# mde_v1.net
KiCad netlist of a schematic drawn in EAGLE
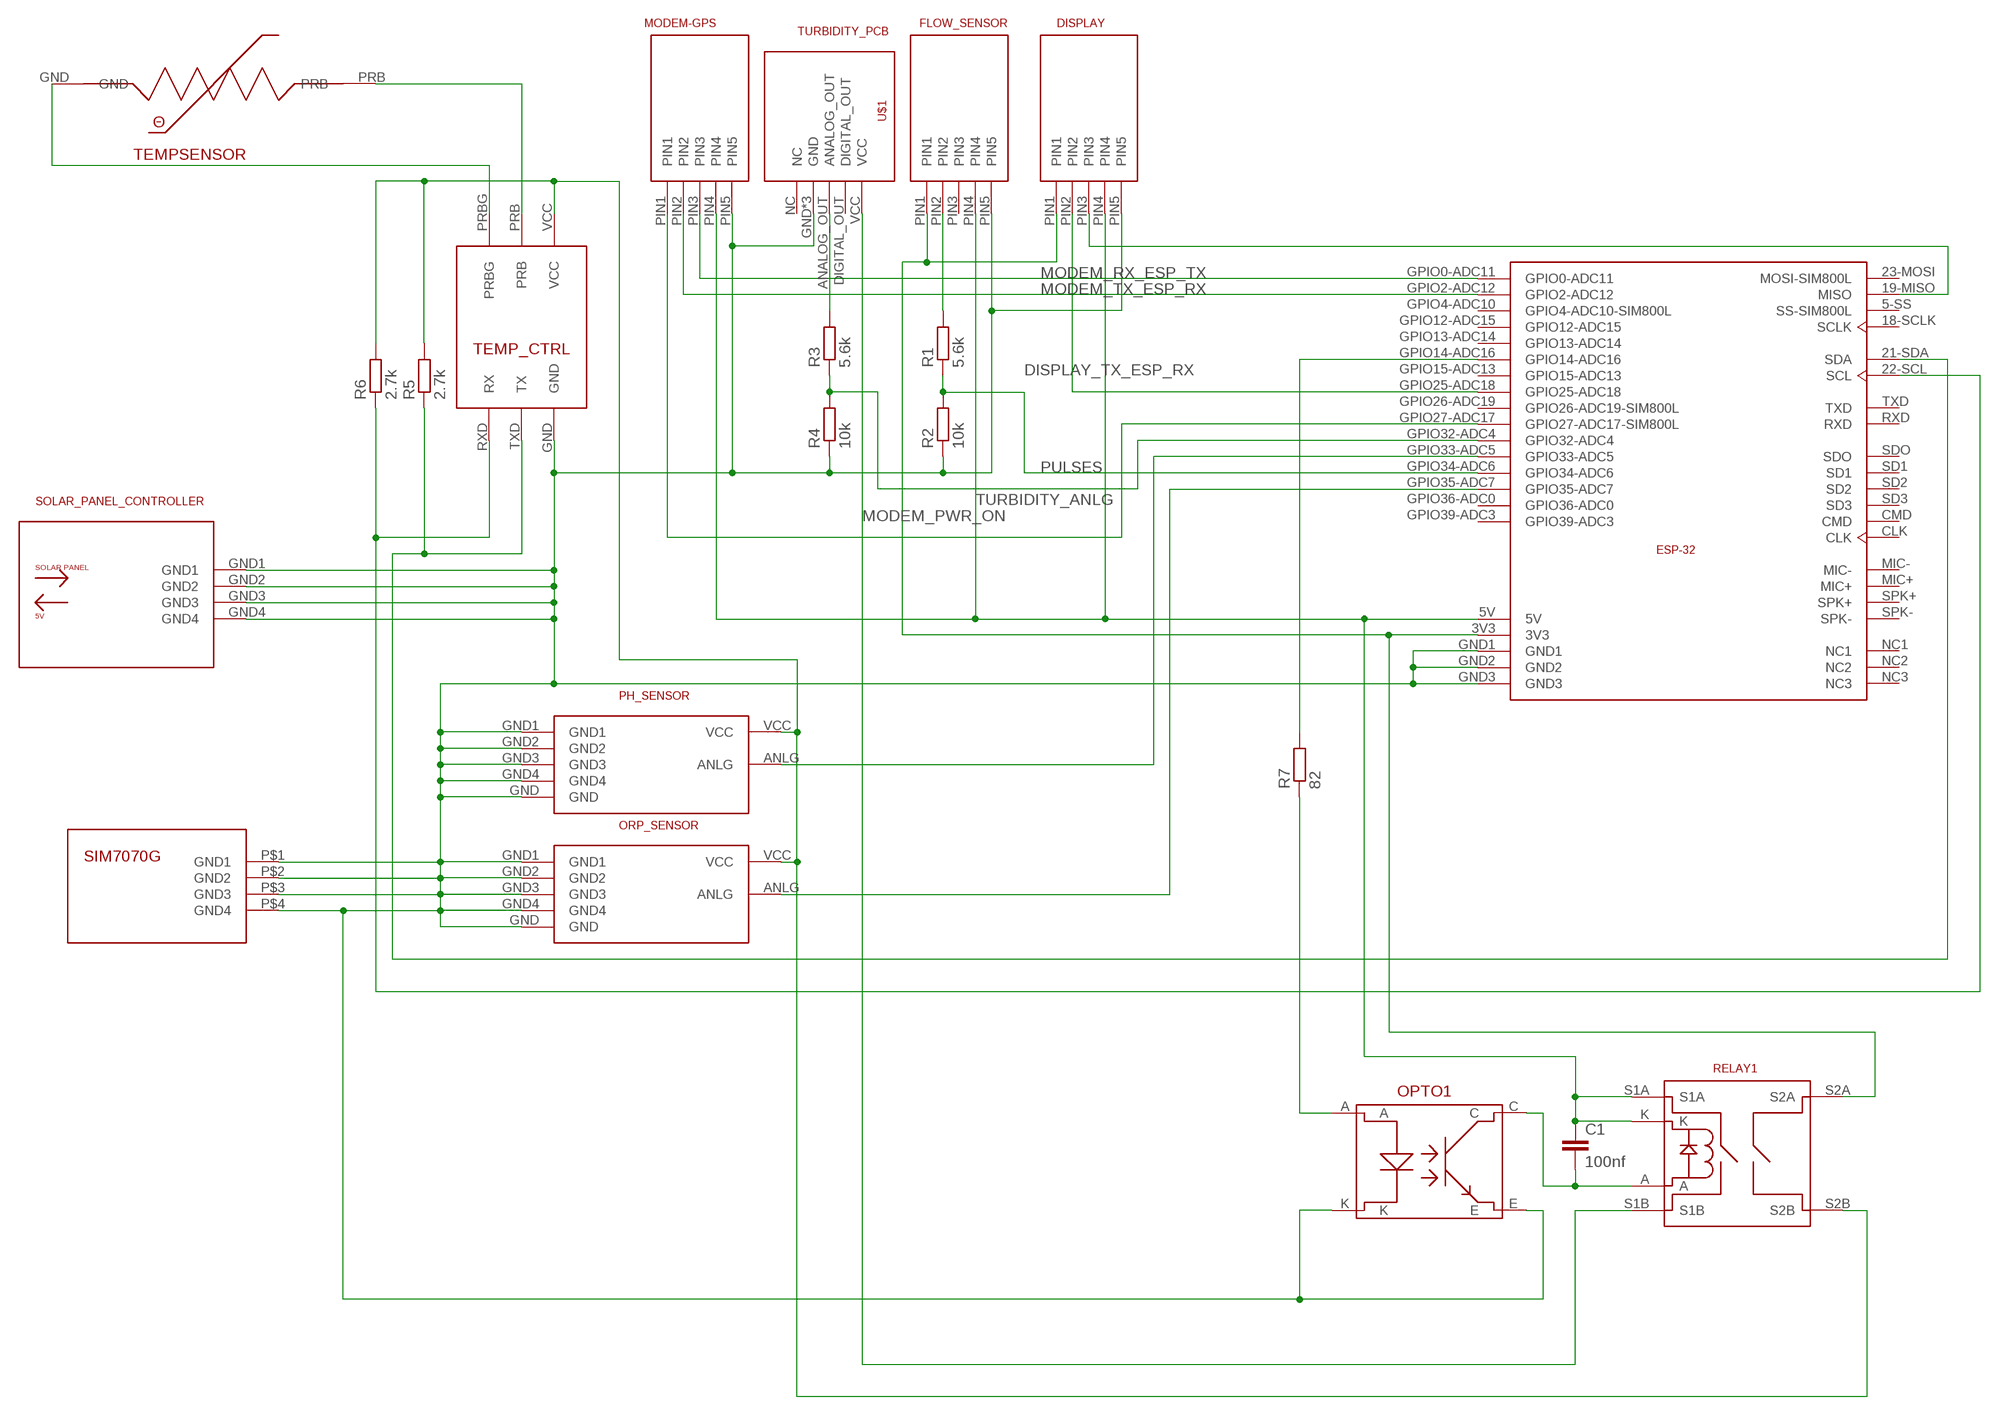
[diagram p0: schematic, sheet 1]

(export (version "E")
  (design (tool "Eeschema 10.0.6"))
  (components
    (comp (ref "C1")
      (value "100nf")
      (footprint "eagle-import:C2.5-3")
      (libsource (lib "eagle-import") (part "C2,5-3"))
    )
    (comp (ref "DISPLAY")
      (value "CONNECTOR-JSTXH-5")
      (footprint "eagle-import:CONNECTOR-JSTXH-5")
      (libsource (lib "eagle-import") (part "CONNECTOR-JSTXH-5"))
    )
    (comp (ref "ESP-32")
      (value "ESP32-TTGO-SIM800L")
      (footprint "eagle-import:ESP32-TTGO-SIM800L")
      (libsource (lib "eagle-import") (part "ESP32-TTGO-SIM800L"))
    )
    (comp (ref "FLOW_SENSOR")
      (value "CONNECTOR-JSTXH-5")
      (footprint "eagle-import:CONNECTOR-JSTXH-5")
      (libsource (lib "eagle-import") (part "CONNECTOR-JSTXH-5"))
    )
    (comp (ref "MODEM-GPS")
      (value "CONNECTOR-JSTXH-5")
      (footprint "eagle-import:CONNECTOR-JSTXH-5")
      (libsource (lib "eagle-import") (part "CONNECTOR-JSTXH-5"))
    )
    (comp (ref "OPTO1")
      (value "K817P")
      (footprint "eagle-import:K817P")
      (libsource (lib "eagle-import") (part "K817P"))
    )
    (comp (ref "ORP_SENSOR")
      (value "GRAVITY-PCB")
      (footprint "eagle-import:GRAVITY-PCB")
      (libsource (lib "eagle-import") (part "GRAVITY-PCB"))
    )
    (comp (ref "PH_SENSOR")
      (value "GRAVITY-PCB")
      (footprint "eagle-import:GRAVITY-PCB")
      (libsource (lib "eagle-import") (part "GRAVITY-PCB"))
    )
    (comp (ref "R1")
      (value "5.6k")
      (footprint "eagle-import:0207_10")
      (libsource (lib "eagle-import") (part "R-EU_0207/10"))
    )
    (comp (ref "R2")
      (value "10k")
      (footprint "eagle-import:0207_10")
      (libsource (lib "eagle-import") (part "R-EU_0207/10"))
    )
    (comp (ref "R3")
      (value "5.6k")
      (footprint "eagle-import:0207_10")
      (libsource (lib "eagle-import") (part "R-EU_0207/10"))
    )
    (comp (ref "R4")
      (value "10k")
      (footprint "eagle-import:0207_10")
      (libsource (lib "eagle-import") (part "R-EU_0207/10"))
    )
    (comp (ref "R5")
      (value "2.7k")
      (footprint "eagle-import:0207_10")
      (libsource (lib "eagle-import") (part "R-EU_0207/10"))
    )
    (comp (ref "R6")
      (value "2.7k")
      (footprint "eagle-import:0207_10")
      (libsource (lib "eagle-import") (part "R-EU_0207/10"))
    )
    (comp (ref "R7")
      (value "82")
      (footprint "eagle-import:0207_10")
      (libsource (lib "eagle-import") (part "R-EU_0207/10"))
    )
    (comp (ref "RELAY1")
      (value "DIP05-2A72-21D")
      (footprint "eagle-import:DIP05-2A72-21D")
      (libsource (lib "eagle-import") (part "DIP05-2A72-21D"))
    )
    (comp (ref "SIM7070G")
      (value "SIM7070G")
      (footprint "eagle-import:SIM7070G")
      (libsource (lib "eagle-import") (part "SIM7070G"))
    )
    (comp (ref "SOLAR_PANEL_CONTROLLER")
      (value "DFR0559")
      (footprint "eagle-import:DFR0559")
      (libsource (lib "eagle-import") (part "DFR0559"))
    )
    (comp (ref "TEMPSENSOR")
      (value "TEMP-PROBE")
      (footprint "eagle-import:TEMP-PROBE")
      (libsource (lib "eagle-import") (part "TEMP-PROBE"))
    )
    (comp (ref "TEMP_CTRL")
      (value "EZO-RTD")
      (footprint "eagle-import:EZO-RTD")
      (libsource (lib "eagle-import") (part "EZO-RTD"))
    )
    (comp (ref "U$1")
      (value "TURBIDITY_PCB")
      (footprint "eagle-import:TURBIDITY_PCB")
      (libsource (lib "eagle-import") (part "TURBIDITY_PCB"))
    )
  )
  (nets
    (net (code "1") (name "/DISPLAY_TX_ESP_RX") (class "Default")
      (node (ref "DISPLAY") (pin "PIN2") (pinfunction "PIN2_PIN2") (pintype "bidirectional"))
      (node (ref "ESP-32") (pin "GPIO25-ADC18") (pinfunction "GPIO25-ADC18_GPIO25-ADC18") (pintype "bidirectional"))
    )
    (net (code "2") (name "/MODEM_PWR_ON") (class "Default")
      (node (ref "ESP-32") (pin "GPIO27-ADC17") (pinfunction "GPIO27-ADC17-SIM800L_GPIO27-ADC17") (pintype "bidirectional"))
      (node (ref "MODEM-GPS") (pin "PIN1") (pinfunction "PIN1_PIN1") (pintype "bidirectional"))
    )
    (net (code "3") (name "/MODEM_RX_ESP_TX") (class "Default")
      (node (ref "ESP-32") (pin "GPIO0-ADC11") (pinfunction "GPIO0-ADC11_GPIO0-ADC11") (pintype "bidirectional"))
      (node (ref "MODEM-GPS") (pin "PIN3") (pinfunction "PIN3_PIN3") (pintype "bidirectional"))
    )
    (net (code "4") (name "/MODEM_TX_ESP_RX") (class "Default")
      (node (ref "ESP-32") (pin "GPIO2-ADC12") (pinfunction "GPIO2-ADC12_GPIO2-ADC12") (pintype "bidirectional"))
      (node (ref "MODEM-GPS") (pin "PIN2") (pinfunction "PIN2_PIN2") (pintype "bidirectional"))
    )
    (net (code "5") (name "/PULSES") (class "Default")
      (node (ref "ESP-32") (pin "GPIO34-ADC6") (pinfunction "GPIO34-ADC6_GPIO34-ADC6") (pintype "bidirectional"))
      (node (ref "R1") (pin "1") (pinfunction "1_1") (pintype "passive"))
      (node (ref "R2") (pin "2") (pinfunction "2_2") (pintype "passive"))
    )
    (net (code "6") (name "/TURBIDITY_ANLG") (class "Default")
      (node (ref "ESP-32") (pin "GPIO32-ADC4") (pinfunction "GPIO32-ADC4_GPIO32-ADC4") (pintype "bidirectional"))
      (node (ref "R3") (pin "1") (pinfunction "1_1") (pintype "passive"))
      (node (ref "R4") (pin "2") (pinfunction "2_2") (pintype "passive"))
    )
    (net (code "7") (name "Net-(C1-Pad1)") (class "Default")
      (node (ref "C1") (pin "1") (pinfunction "1_1") (pintype "passive"))
      (node (ref "DISPLAY") (pin "PIN4") (pinfunction "PIN4_PIN4") (pintype "bidirectional"))
      (node (ref "ESP-32") (pin "5V") (pinfunction "5V_5V") (pintype "power_in"))
      (node (ref "FLOW_SENSOR") (pin "PIN4") (pinfunction "PIN4_PIN4") (pintype "bidirectional"))
      (node (ref "MODEM-GPS") (pin "PIN4") (pinfunction "PIN4_PIN4") (pintype "bidirectional"))
      (node (ref "RELAY1") (pin "K") (pinfunction "K_K") (pintype "bidirectional"))
      (node (ref "RELAY1") (pin "S1A") (pinfunction "S1A_S1A") (pintype "bidirectional"))
    )
    (net (code "8") (name "Net-(C1-Pad2)") (class "Default")
      (node (ref "C1") (pin "2") (pinfunction "2_2") (pintype "passive"))
      (node (ref "OPTO1") (pin "C") (pinfunction "C_C") (pintype "bidirectional"))
      (node (ref "RELAY1") (pin "A") (pinfunction "A_A") (pintype "bidirectional"))
    )
    (net (code "9") (name "Net-(DISPLAY-PadPIN1)") (class "Default")
      (node (ref "DISPLAY") (pin "PIN1") (pinfunction "PIN1_PIN1") (pintype "bidirectional"))
      (node (ref "ESP-32") (pin "3V3") (pinfunction "3V3_3V3") (pintype "power_in"))
      (node (ref "FLOW_SENSOR") (pin "PIN1") (pinfunction "PIN1_PIN1") (pintype "bidirectional"))
      (node (ref "RELAY1") (pin "S2A") (pinfunction "S2A_S2A") (pintype "bidirectional"))
    )
    (net (code "10") (name "Net-(ESP-32-MISO)") (class "Default")
      (node (ref "DISPLAY") (pin "PIN3") (pinfunction "PIN3_PIN3") (pintype "bidirectional"))
      (node (ref "ESP-32") (pin "19-MISO") (pinfunction "MISO_19-MISO") (pintype "input"))
    )
    (net (code "11") (name "Net-(ESP-32-PadGPIO14-ADC16)") (class "Default")
      (node (ref "ESP-32") (pin "GPIO14-ADC16") (pinfunction "GPIO14-ADC16_GPIO14-ADC16") (pintype "bidirectional"))
      (node (ref "R7") (pin "2") (pinfunction "2_2") (pintype "passive"))
    )
    (net (code "12") (name "Net-(ESP-32-PadGPIO33-ADC5)") (class "Default")
      (node (ref "ESP-32") (pin "GPIO33-ADC5") (pinfunction "GPIO33-ADC5_GPIO33-ADC5") (pintype "bidirectional"))
      (node (ref "PH_SENSOR") (pin "ANLG") (pinfunction "ANLG_ANLG") (pintype "output"))
    )
    (net (code "13") (name "Net-(ESP-32-PadGPIO35-ADC7)") (class "Default")
      (node (ref "ESP-32") (pin "GPIO35-ADC7") (pinfunction "GPIO35-ADC7_GPIO35-ADC7") (pintype "bidirectional"))
      (node (ref "ORP_SENSOR") (pin "ANLG") (pinfunction "ANLG_ANLG") (pintype "output"))
    )
    (net (code "14") (name "Net-(ESP-32-SCL)") (class "Default")
      (node (ref "ESP-32") (pin "22-SCL") (pinfunction "SCL_22-SCL") (pintype "bidirectional"))
      (node (ref "R6") (pin "1") (pinfunction "1_1") (pintype "passive"))
      (node (ref "TEMP_CTRL") (pin "RXD") (pinfunction "RX_RXD") (pintype "input"))
    )
    (net (code "15") (name "Net-(ESP-32-SDA)") (class "Default")
      (node (ref "ESP-32") (pin "21-SDA") (pinfunction "SDA_21-SDA") (pintype "bidirectional"))
      (node (ref "R5") (pin "1") (pinfunction "1_1") (pintype "passive"))
      (node (ref "TEMP_CTRL") (pin "TXD") (pinfunction "TX_TXD") (pintype "output"))
    )
    (net (code "16") (name "Net-(FLOW_SENSOR-PadPIN2)") (class "Default")
      (node (ref "FLOW_SENSOR") (pin "PIN2") (pinfunction "PIN2_PIN2") (pintype "bidirectional"))
      (node (ref "R1") (pin "2") (pinfunction "2_2") (pintype "passive"))
    )
    (net (code "17") (name "Net-(OPTO1-PadA)") (class "Default")
      (node (ref "OPTO1") (pin "A") (pinfunction "A_A") (pintype "bidirectional"))
      (node (ref "R7") (pin "1") (pinfunction "1_1") (pintype "passive"))
    )
    (net (code "18") (name "Net-(ORP_SENSOR-PadVCC)") (class "Default")
      (node (ref "ORP_SENSOR") (pin "VCC") (pinfunction "VCC_VCC") (pintype "power_in"))
      (node (ref "PH_SENSOR") (pin "VCC") (pinfunction "VCC_VCC") (pintype "power_in"))
      (node (ref "R5") (pin "2") (pinfunction "2_2") (pintype "passive"))
      (node (ref "R6") (pin "2") (pinfunction "2_2") (pintype "passive"))
      (node (ref "RELAY1") (pin "S2B") (pinfunction "S2B_S2B") (pintype "bidirectional"))
      (node (ref "TEMP_CTRL") (pin "VCC") (pinfunction "VCC_VCC") (pintype "power_in"))
    )
    (net (code "19") (name "Net-(R3-Pad2)") (class "Default")
      (node (ref "R3") (pin "2") (pinfunction "2_2") (pintype "passive"))
      (node (ref "U$1") (pin "ANALOG_OUT") (pinfunction "ANALOG_OUT_ANALOG_OUT") (pintype "output"))
    )
    (net (code "20") (name "Net-(RELAY1-PadS1B)") (class "Default")
      (node (ref "RELAY1") (pin "S1B") (pinfunction "S1B_S1B") (pintype "bidirectional"))
      (node (ref "U$1") (pin "VCC") (pinfunction "VCC_VCC") (pintype "power_in"))
    )
    (net (code "21") (name "Net-(SIM7070G-GND1)") (class "Default")
      (node (ref "DISPLAY") (pin "PIN5") (pinfunction "PIN5_PIN5") (pintype "bidirectional"))
      (node (ref "ESP-32") (pin "GND1") (pinfunction "GND1_GND1") (pintype "power_in"))
      (node (ref "ESP-32") (pin "GND2") (pinfunction "GND2_GND2") (pintype "power_in"))
      (node (ref "ESP-32") (pin "GND3") (pinfunction "GND3_GND3") (pintype "power_in"))
      (node (ref "FLOW_SENSOR") (pin "PIN5") (pinfunction "PIN5_PIN5") (pintype "bidirectional"))
      (node (ref "MODEM-GPS") (pin "PIN5") (pinfunction "PIN5_PIN5") (pintype "bidirectional"))
      (node (ref "OPTO1") (pin "E") (pinfunction "E_E") (pintype "bidirectional"))
      (node (ref "OPTO1") (pin "K") (pinfunction "K_K") (pintype "bidirectional"))
      (node (ref "ORP_SENSOR") (pin "GND") (pinfunction "GND_GND") (pintype "power_in"))
      (node (ref "ORP_SENSOR") (pin "GND1") (pinfunction "GND1_GND1") (pintype "power_in"))
      (node (ref "ORP_SENSOR") (pin "GND2") (pinfunction "GND2_GND2") (pintype "power_in"))
      (node (ref "ORP_SENSOR") (pin "GND3") (pinfunction "GND3_GND3") (pintype "power_in"))
      (node (ref "ORP_SENSOR") (pin "GND4") (pinfunction "GND4_GND4") (pintype "power_in"))
      (node (ref "PH_SENSOR") (pin "GND") (pinfunction "GND_GND") (pintype "power_in"))
      (node (ref "PH_SENSOR") (pin "GND1") (pinfunction "GND1_GND1") (pintype "power_in"))
      (node (ref "PH_SENSOR") (pin "GND2") (pinfunction "GND2_GND2") (pintype "power_in"))
      (node (ref "PH_SENSOR") (pin "GND3") (pinfunction "GND3_GND3") (pintype "power_in"))
      (node (ref "PH_SENSOR") (pin "GND4") (pinfunction "GND4_GND4") (pintype "power_in"))
      (node (ref "R2") (pin "1") (pinfunction "1_1") (pintype "passive"))
      (node (ref "R4") (pin "1") (pinfunction "1_1") (pintype "passive"))
      (node (ref "SIM7070G") (pin "P$1") (pinfunction "GND1_P$1") (pintype "bidirectional"))
      (node (ref "SIM7070G") (pin "P$2") (pinfunction "GND2_P$2") (pintype "bidirectional"))
      (node (ref "SIM7070G") (pin "P$3") (pinfunction "GND3_P$3") (pintype "bidirectional"))
      (node (ref "SIM7070G") (pin "P$4") (pinfunction "GND4_P$4") (pintype "bidirectional"))
      (node (ref "SOLAR_PANEL_CONTROLLER") (pin "GND1") (pinfunction "GND1_GND1") (pintype "power_in"))
      (node (ref "SOLAR_PANEL_CONTROLLER") (pin "GND2") (pinfunction "GND2_GND2") (pintype "power_in"))
      (node (ref "SOLAR_PANEL_CONTROLLER") (pin "GND3") (pinfunction "GND3_GND3") (pintype "power_in"))
      (node (ref "SOLAR_PANEL_CONTROLLER") (pin "GND4") (pinfunction "GND4_GND4") (pintype "power_in"))
      (node (ref "TEMP_CTRL") (pin "GND") (pinfunction "GND_GND") (pintype "power_in"))
      (node (ref "U$1") (pin "GND") (pinfunction "GND_GND") (pintype "power_in"))
      (node (ref "U$1") (pin "P$1") (pinfunction "GND_P$1") (pintype "power_in"))
      (node (ref "U$1") (pin "P$2") (pinfunction "GND_P$2") (pintype "power_in"))
    )
    (net (code "22") (name "Net-(TEMPSENSOR-PadGND)") (class "Default")
      (node (ref "TEMPSENSOR") (pin "GND") (pinfunction "GND_GND") (pintype "passive"))
      (node (ref "TEMP_CTRL") (pin "PRBG") (pinfunction "PRBG_PRBG") (pintype "passive"))
    )
    (net (code "23") (name "Net-(TEMPSENSOR-PadPRB)") (class "Default")
      (node (ref "TEMPSENSOR") (pin "PRB") (pinfunction "PRB_PRB") (pintype "passive"))
      (node (ref "TEMP_CTRL") (pin "PRB") (pinfunction "PRB_PRB") (pintype "passive"))
    )
    (net (code "24") (name "unconnected-(ESP-32-GPIO4-ADC10-SIM800L-PadGPIO4-ADC10)") (class "Default")
      (node (ref "ESP-32") (pin "GPIO4-ADC10") (pinfunction "GPIO4-ADC10-SIM800L_GPIO4-ADC10") (pintype "bidirectional"))
    )
    (net (code "25") (name "unconnected-(ESP-32-GPIO26-ADC19-SIM800L-PadGPIO26-ADC19)") (class "Default")
      (node (ref "ESP-32") (pin "GPIO26-ADC19") (pinfunction "GPIO26-ADC19-SIM800L_GPIO26-ADC19") (pintype "bidirectional"))
    )
    (net (code "26") (name "unconnected-(ESP-32-MOSI-SIM800L-Pad23-MOSI)") (class "Default")
      (node (ref "ESP-32") (pin "23-MOSI") (pinfunction "MOSI-SIM800L_23-MOSI") (pintype "output"))
    )
    (net (code "27") (name "unconnected-(ESP-32-PadCLK)") (class "Default")
      (node (ref "ESP-32") (pin "CLK") (pinfunction "CLK_CLK") (pintype "output"))
    )
    (net (code "28") (name "unconnected-(ESP-32-PadCMD)") (class "Default")
      (node (ref "ESP-32") (pin "CMD") (pinfunction "CMD_CMD") (pintype "bidirectional"))
    )
    (net (code "29") (name "unconnected-(ESP-32-PadGPIO12-ADC15)") (class "Default")
      (node (ref "ESP-32") (pin "GPIO12-ADC15") (pinfunction "GPIO12-ADC15_GPIO12-ADC15") (pintype "bidirectional"))
    )
    (net (code "30") (name "unconnected-(ESP-32-PadGPIO13-ADC14)") (class "Default")
      (node (ref "ESP-32") (pin "GPIO13-ADC14") (pinfunction "GPIO13-ADC14_GPIO13-ADC14") (pintype "bidirectional"))
    )
    (net (code "31") (name "unconnected-(ESP-32-PadGPIO15-ADC13)") (class "Default")
      (node (ref "ESP-32") (pin "GPIO15-ADC13") (pinfunction "GPIO15-ADC13_GPIO15-ADC13") (pintype "bidirectional"))
    )
    (net (code "32") (name "unconnected-(ESP-32-PadGPIO36-ADC0)") (class "Default")
      (node (ref "ESP-32") (pin "GPIO36-ADC0") (pinfunction "GPIO36-ADC0_GPIO36-ADC0") (pintype "bidirectional"))
    )
    (net (code "33") (name "unconnected-(ESP-32-PadGPIO39-ADC3)") (class "Default")
      (node (ref "ESP-32") (pin "GPIO39-ADC3") (pinfunction "GPIO39-ADC3_GPIO39-ADC3") (pintype "bidirectional"))
    )
    (net (code "34") (name "unconnected-(ESP-32-PadMIC+)") (class "Default")
      (node (ref "ESP-32") (pin "MIC+") (pinfunction "MIC+_MIC+") (pintype "input"))
    )
    (net (code "35") (name "unconnected-(ESP-32-PadMIC-)") (class "Default")
      (node (ref "ESP-32") (pin "MIC-") (pinfunction "MIC-_MIC-") (pintype "input"))
    )
    (net (code "36") (name "unconnected-(ESP-32-PadNC1)") (class "Default")
      (node (ref "ESP-32") (pin "NC1") (pinfunction "NC1_NC1") (pintype "no_connect"))
    )
    (net (code "37") (name "unconnected-(ESP-32-PadNC2)") (class "Default")
      (node (ref "ESP-32") (pin "NC2") (pinfunction "NC2_NC2") (pintype "no_connect"))
    )
    (net (code "38") (name "unconnected-(ESP-32-PadNC3)") (class "Default")
      (node (ref "ESP-32") (pin "NC3") (pinfunction "NC3_NC3") (pintype "no_connect"))
    )
    (net (code "39") (name "unconnected-(ESP-32-PadRXD)") (class "Default")
      (node (ref "ESP-32") (pin "RXD") (pinfunction "RXD_RXD") (pintype "input"))
    )
    (net (code "40") (name "unconnected-(ESP-32-PadSD1)") (class "Default")
      (node (ref "ESP-32") (pin "SD1") (pinfunction "SD1_SD1") (pintype "bidirectional"))
    )
    (net (code "41") (name "unconnected-(ESP-32-PadSD2)") (class "Default")
      (node (ref "ESP-32") (pin "SD2") (pinfunction "SD2_SD2") (pintype "bidirectional"))
    )
    (net (code "42") (name "unconnected-(ESP-32-PadSD3)") (class "Default")
      (node (ref "ESP-32") (pin "SD3") (pinfunction "SD3_SD3") (pintype "bidirectional"))
    )
    (net (code "43") (name "unconnected-(ESP-32-PadSDO)") (class "Default")
      (node (ref "ESP-32") (pin "SDO") (pinfunction "SDO_SDO") (pintype "output"))
    )
    (net (code "44") (name "unconnected-(ESP-32-PadSPK+)") (class "Default")
      (node (ref "ESP-32") (pin "SPK+") (pinfunction "SPK+_SPK+") (pintype "output"))
    )
    (net (code "45") (name "unconnected-(ESP-32-PadSPK-)") (class "Default")
      (node (ref "ESP-32") (pin "SPK-") (pinfunction "SPK-_SPK-") (pintype "output"))
    )
    (net (code "46") (name "unconnected-(ESP-32-PadTXD)") (class "Default")
      (node (ref "ESP-32") (pin "TXD") (pinfunction "TXD_TXD") (pintype "output"))
    )
    (net (code "47") (name "unconnected-(ESP-32-SCLK-Pad18-SCLK)") (class "Default")
      (node (ref "ESP-32") (pin "18-SCLK") (pinfunction "SCLK_18-SCLK") (pintype "output"))
    )
    (net (code "48") (name "unconnected-(ESP-32-SS-SIM800L-Pad5-SS)") (class "Default")
      (node (ref "ESP-32") (pin "5-SS") (pinfunction "SS-SIM800L_5-SS") (pintype "output"))
    )
    (net (code "49") (name "unconnected-(FLOW_SENSOR-PadPIN3)") (class "Default")
      (node (ref "FLOW_SENSOR") (pin "PIN3") (pinfunction "PIN3_PIN3") (pintype "bidirectional"))
    )
    (net (code "50") (name "unconnected-(U$1-PadDIGITAL_OUT)") (class "Default")
      (node (ref "U$1") (pin "DIGITAL_OUT") (pinfunction "DIGITAL_OUT_DIGITAL_OUT") (pintype "output"))
    )
    (net (code "51") (name "unconnected-(U$1-PadNC)") (class "Default")
      (node (ref "U$1") (pin "NC") (pinfunction "NC_NC") (pintype "no_connect"))
    )
  )
)
